# mSD-Breakout_v11.net
KiCad netlist of a schematic drawn in EAGLE
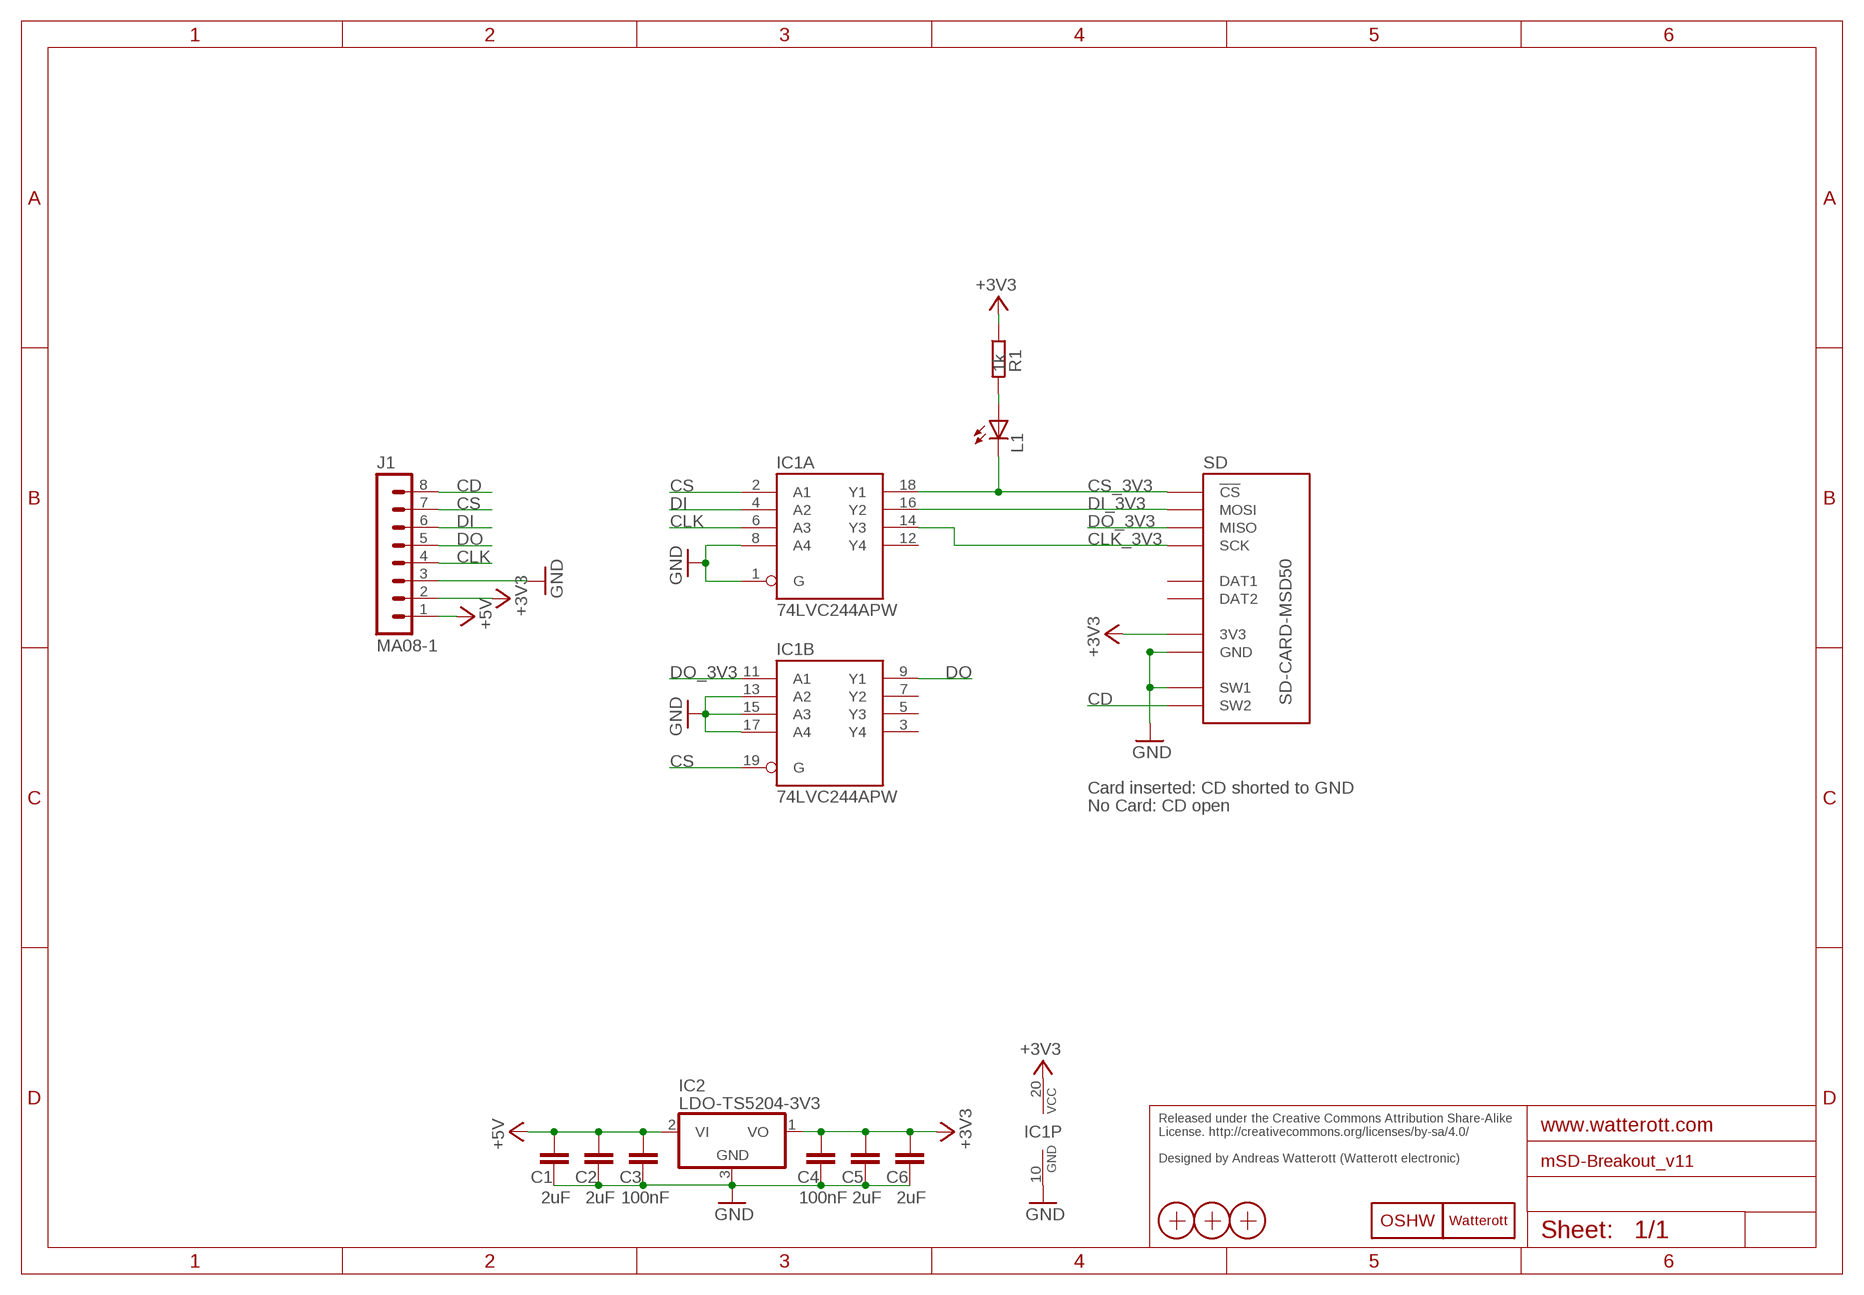
[diagram p0: schematic, sheet 1]

(export (version "E")
  (design (tool "Eeschema 10.0.6"))
  (components
    (comp (ref "C1")
      (value "2uF")
      (footprint "eagle-import:C0402")
      (libsource (lib "eagle-import") (part "C-EUC0402"))
    )
    (comp (ref "C2")
      (value "2uF")
      (footprint "eagle-import:C0402")
      (libsource (lib "eagle-import") (part "C-EUC0402"))
    )
    (comp (ref "C3")
      (value "100nF")
      (footprint "eagle-import:C0402")
      (libsource (lib "eagle-import") (part "C-EUC0402"))
    )
    (comp (ref "C4")
      (value "100nF")
      (footprint "eagle-import:C0402")
      (libsource (lib "eagle-import") (part "C-EUC0402"))
    )
    (comp (ref "C5")
      (value "2uF")
      (footprint "eagle-import:C0402")
      (libsource (lib "eagle-import") (part "C-EUC0402"))
    )
    (comp (ref "C6")
      (value "2uF")
      (footprint "eagle-import:C0402")
      (libsource (lib "eagle-import") (part "C-EUC0402"))
    )
    (comp (ref "IC1")
      (value "74LVC244APW")
      (footprint "eagle-import:TSSOP20")
      (libsource (lib "eagle-import") (part "74244PWLVC"))
    )
    (comp (ref "IC2")
      (value "LDO-TS5204-3V3")
      (footprint "eagle-import:SOT23")
      (libsource (lib "eagle-import") (part "LDO-TS5204"))
    )
    (comp (ref "J1")
      (value "MA08-1")
      (footprint "eagle-import:MA08-1")
      (libsource (lib "eagle-import") (part "MA08-1"))
    )
    (comp (ref "L1")
      (value "LED-0603")
      (footprint "eagle-import:C0603")
      (libsource (lib "eagle-import") (part "LED-0603"))
    )
    (comp (ref "LOGO1")
      (value "OSHW_LOGOX0100")
      (footprint "eagle-import:OSHW_6X100")
      (libsource (lib "eagle-import") (part "OSHW_LOGOX0100"))
    )
    (comp (ref "LOGO2")
      (value "LOGO-S_PLACE_S")
      (footprint "eagle-import:SPARK_TPLACE_S")
      (libsource (lib "eagle-import") (part "LOGO-S_PLACE_S"))
    )
    (comp (ref "R1")
      (value "1k")
      (footprint "eagle-import:R0402")
      (libsource (lib "eagle-import") (part "R-EU_R0402"))
    )
    (comp (ref "SD")
      (value "SD-CARD-MSD50")
      (footprint "eagle-import:SD_5031821853")
      (libsource (lib "eagle-import") (part "SD-CARD-MSD50"))
    )
    (comp (ref "X1")
      (value "PASSER-07")
      (footprint "eagle-import:PASSER_07MM")
      (libsource (lib "eagle-import") (part "PASSER-07"))
    )
    (comp (ref "X2")
      (value "PASSER-07")
      (footprint "eagle-import:PASSER_07MM")
      (libsource (lib "eagle-import") (part "PASSER-07"))
    )
    (comp (ref "X3")
      (value "PASSER-07")
      (footprint "eagle-import:PASSER_07MM")
      (libsource (lib "eagle-import") (part "PASSER-07"))
    )
  )
  (nets
    (net (code "1") (name "+3V3") (class "Default")
      (node (ref "C4") (pin "1") (pinfunction "1_1") (pintype "passive"))
      (node (ref "C5") (pin "1") (pinfunction "1_1") (pintype "passive"))
      (node (ref "C6") (pin "1") (pinfunction "1_1") (pintype "passive"))
      (node (ref "IC1") (pin "20") (pinfunction "VCC_20") (pintype "power_in"))
      (node (ref "IC2") (pin "1") (pinfunction "VO_1") (pintype "passive"))
      (node (ref "J1") (pin "2") (pinfunction "2_2") (pintype "passive"))
      (node (ref "R1") (pin "1") (pinfunction "1_1") (pintype "passive"))
      (node (ref "SD") (pin "VCC") (pinfunction "3V3_VCC") (pintype "bidirectional"))
    )
    (net (code "2") (name "+5V") (class "Default")
      (node (ref "C1") (pin "1") (pinfunction "1_1") (pintype "passive"))
      (node (ref "C2") (pin "1") (pinfunction "1_1") (pintype "passive"))
      (node (ref "C3") (pin "1") (pinfunction "1_1") (pintype "passive"))
      (node (ref "IC2") (pin "2") (pinfunction "VI_2") (pintype "input"))
      (node (ref "J1") (pin "1") (pinfunction "1_1") (pintype "passive"))
    )
    (net (code "3") (name "/CD") (class "Default")
      (node (ref "J1") (pin "8") (pinfunction "8_8") (pintype "passive"))
      (node (ref "SD") (pin "SW2") (pinfunction "SW2_SW2") (pintype "bidirectional"))
    )
    (net (code "4") (name "/CLK") (class "Default")
      (node (ref "IC1") (pin "6") (pinfunction "A3_6") (pintype "input"))
      (node (ref "J1") (pin "4") (pinfunction "4_4") (pintype "passive"))
    )
    (net (code "5") (name "/CLK_3V3") (class "Default")
      (node (ref "IC1") (pin "14") (pinfunction "Y3_14") (pintype "tri_state"))
      (node (ref "SD") (pin "SCK") (pinfunction "SCK_SCK") (pintype "bidirectional"))
    )
    (net (code "6") (name "/CS") (class "Default")
      (node (ref "IC1") (pin "19") (pinfunction "G_19") (pintype "input"))
      (node (ref "IC1") (pin "2") (pinfunction "A1_2") (pintype "input"))
      (node (ref "J1") (pin "7") (pinfunction "7_7") (pintype "passive"))
    )
    (net (code "7") (name "/CS_3V3") (class "Default")
      (node (ref "IC1") (pin "18") (pinfunction "Y1_18") (pintype "tri_state"))
      (node (ref "L1") (pin "C") (pinfunction "C_C") (pintype "passive"))
      (node (ref "SD") (pin "CS") (pinfunction "~{CS}_CS") (pintype "bidirectional"))
    )
    (net (code "8") (name "/DI") (class "Default")
      (node (ref "IC1") (pin "4") (pinfunction "A2_4") (pintype "input"))
      (node (ref "J1") (pin "6") (pinfunction "6_6") (pintype "passive"))
    )
    (net (code "9") (name "/DI_3V3") (class "Default")
      (node (ref "IC1") (pin "16") (pinfunction "Y2_16") (pintype "tri_state"))
      (node (ref "SD") (pin "MOSI") (pinfunction "MOSI_MOSI") (pintype "bidirectional"))
    )
    (net (code "10") (name "/DO") (class "Default")
      (node (ref "IC1") (pin "9") (pinfunction "Y1_9") (pintype "tri_state"))
      (node (ref "J1") (pin "5") (pinfunction "5_5") (pintype "passive"))
    )
    (net (code "11") (name "/DO_3V3") (class "Default")
      (node (ref "IC1") (pin "11") (pinfunction "A1_11") (pintype "input"))
      (node (ref "SD") (pin "MISO") (pinfunction "MISO_MISO") (pintype "bidirectional"))
    )
    (net (code "12") (name "GND") (class "Default")
      (node (ref "C1") (pin "2") (pinfunction "2_2") (pintype "passive"))
      (node (ref "C2") (pin "2") (pinfunction "2_2") (pintype "passive"))
      (node (ref "C3") (pin "2") (pinfunction "2_2") (pintype "passive"))
      (node (ref "C4") (pin "2") (pinfunction "2_2") (pintype "passive"))
      (node (ref "C5") (pin "2") (pinfunction "2_2") (pintype "passive"))
      (node (ref "C6") (pin "2") (pinfunction "2_2") (pintype "passive"))
      (node (ref "IC1") (pin "1") (pinfunction "G_1") (pintype "input"))
      (node (ref "IC1") (pin "10") (pinfunction "GND_10") (pintype "power_in"))
      (node (ref "IC1") (pin "13") (pinfunction "A2_13") (pintype "input"))
      (node (ref "IC1") (pin "15") (pinfunction "A3_15") (pintype "input"))
      (node (ref "IC1") (pin "17") (pinfunction "A4_17") (pintype "input"))
      (node (ref "IC1") (pin "8") (pinfunction "A4_8") (pintype "input"))
      (node (ref "IC2") (pin "3") (pinfunction "GND_3") (pintype "passive"))
      (node (ref "J1") (pin "3") (pinfunction "3_3") (pintype "passive"))
      (node (ref "SD") (pin "GND") (pinfunction "GND_GND") (pintype "bidirectional"))
      (node (ref "SD") (pin "SW1") (pinfunction "SW1_SW1") (pintype "bidirectional"))
    )
    (net (code "13") (name "Net-(L1-PadA)") (class "Default")
      (node (ref "L1") (pin "A") (pinfunction "A_A") (pintype "passive"))
      (node (ref "R1") (pin "2") (pinfunction "2_2") (pintype "passive"))
    )
    (net (code "14") (name "unconnected-(IC1A-Y4-Pad12)") (class "Default")
      (node (ref "IC1") (pin "12") (pinfunction "Y4_12") (pintype "tri_state"))
    )
    (net (code "15") (name "unconnected-(IC1B-Y2-Pad7)") (class "Default")
      (node (ref "IC1") (pin "7") (pinfunction "Y2_7") (pintype "tri_state"))
    )
    (net (code "16") (name "unconnected-(IC1B-Y3-Pad5)") (class "Default")
      (node (ref "IC1") (pin "5") (pinfunction "Y3_5") (pintype "tri_state"))
    )
    (net (code "17") (name "unconnected-(IC1B-Y4-Pad3)") (class "Default")
      (node (ref "IC1") (pin "3") (pinfunction "Y4_3") (pintype "tri_state"))
    )
    (net (code "18") (name "unconnected-(SD-PadDAT1)") (class "Default")
      (node (ref "SD") (pin "DAT1") (pinfunction "DAT1_DAT1") (pintype "bidirectional"))
    )
    (net (code "19") (name "unconnected-(SD-PadDAT2)") (class "Default")
      (node (ref "SD") (pin "DAT2") (pinfunction "DAT2_DAT2") (pintype "bidirectional"))
    )
  )
)
